# small_weather_station.net
KiCad netlist of a schematic drawn in EAGLE
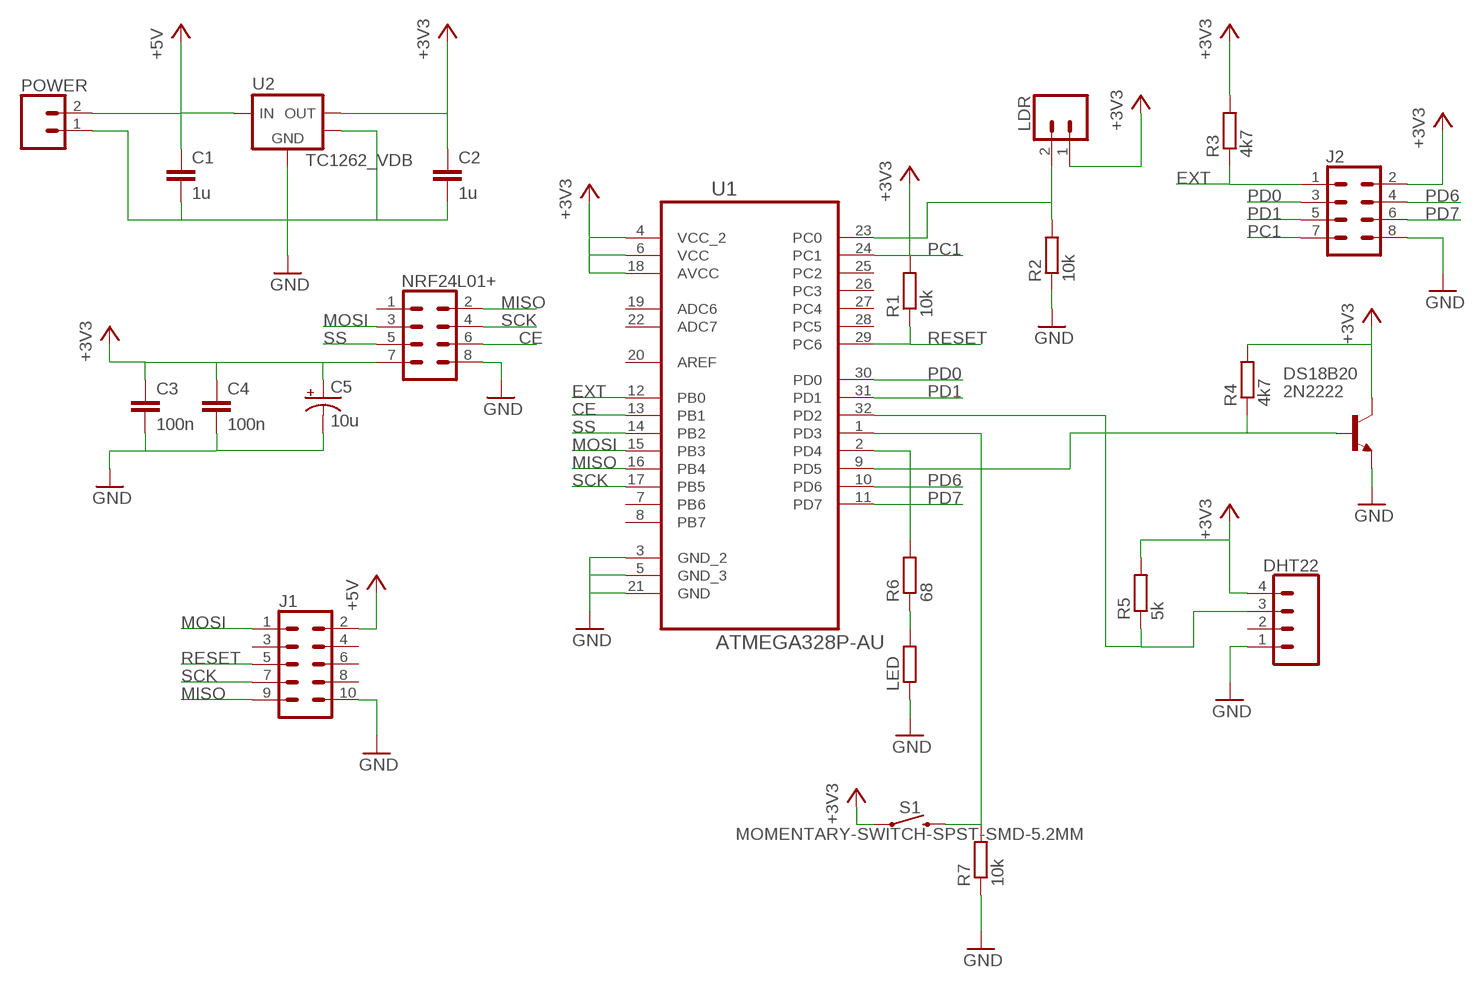
[diagram p0: schematic, sheet 1]

(export (version "E")
  (design (tool "Eeschema 10.0.6"))
  (components
    (comp (ref "C1")
      (value "1u")
      (footprint "eagle-import:C0402")
      (libsource (lib "eagle-import") (part "C-EUC0402"))
    )
    (comp (ref "C2")
      (value "1u")
      (footprint "eagle-import:C0402")
      (libsource (lib "eagle-import") (part "C-EUC0402"))
    )
    (comp (ref "C3")
      (value "100n")
      (footprint "eagle-import:C0402")
      (libsource (lib "eagle-import") (part "C-EUC0402"))
    )
    (comp (ref "C4")
      (value "100n")
      (footprint "eagle-import:C0402")
      (libsource (lib "eagle-import") (part "C-EUC0402"))
    )
    (comp (ref "C5")
      (value "10u")
      (footprint "eagle-import:PANASONIC_D")
      (libsource (lib "eagle-import") (part "CPOL-USD"))
    )
    (comp (ref "DHT22")
      (value "CONN_04")
      (footprint "eagle-import:1X04")
      (libsource (lib "eagle-import") (part "CONN_04"))
    )
    (comp (ref "DS18B20")
      (value "2N2222")
      (footprint "eagle-import:TO92-EBC-OVAL")
      (libsource (lib "eagle-import") (part "2N2222"))
    )
    (comp (ref "J1")
      (value "CONN_05X2SHD-NS")
      (footprint "eagle-import:2X5-SHROUDED-NS")
      (libsource (lib "eagle-import") (part "CONN_05X2SHD-NS"))
    )
    (comp (ref "J2")
      (value "CONN_04X2")
      (footprint "eagle-import:2X4")
      (libsource (lib "eagle-import") (part "CONN_04X2"))
    )
    (comp (ref "LDR")
      (value "CONN_02")
      (footprint "eagle-import:1X02")
      (libsource (lib "eagle-import") (part "CONN_02"))
    )
    (comp (ref "LED")
      (value "R-EU_R0402")
      (footprint "eagle-import:R0402")
      (libsource (lib "eagle-import") (part "R-EU_R0402"))
    )
    (comp (ref "NRF24L01+")
      (value "CONN_04X2")
      (footprint "eagle-import:2X4")
      (libsource (lib "eagle-import") (part "CONN_04X2"))
    )
    (comp (ref "POWER")
      (value "CONN_02")
      (footprint "eagle-import:1X02")
      (libsource (lib "eagle-import") (part "CONN_02"))
    )
    (comp (ref "R1")
      (value "10k")
      (footprint "eagle-import:R0402")
      (libsource (lib "eagle-import") (part "R-EU_R0402"))
    )
    (comp (ref "R2")
      (value "10k")
      (footprint "eagle-import:R0402")
      (libsource (lib "eagle-import") (part "R-EU_R0402"))
    )
    (comp (ref "R3")
      (value "4k7")
      (footprint "eagle-import:R0402")
      (libsource (lib "eagle-import") (part "R-EU_R0402"))
    )
    (comp (ref "R4")
      (value "4k7")
      (footprint "eagle-import:R0402")
      (libsource (lib "eagle-import") (part "R-EU_R0402"))
    )
    (comp (ref "R5")
      (value "5k")
      (footprint "eagle-import:R0402")
      (libsource (lib "eagle-import") (part "R-EU_R0402"))
    )
    (comp (ref "R6")
      (value "68")
      (footprint "eagle-import:R0402")
      (libsource (lib "eagle-import") (part "R-EU_R0402"))
    )
    (comp (ref "R7")
      (value "10k")
      (footprint "eagle-import:R0402")
      (libsource (lib "eagle-import") (part "R-EU_R0402"))
    )
    (comp (ref "S1")
      (value "MOMENTARY-SWITCH-SPST-SMD-5.2MM")
      (footprint "eagle-import:TACTILE_SWITCH_SMD_5.2MM")
      (libsource (lib "eagle-import") (part "MOMENTARY-SWITCH-SPST-SMD-5.2MM"))
    )
    (comp (ref "U1")
      (value "ATMEGA328P-AU")
      (footprint "eagle-import:QFP80P900X900X120-32N")
      (libsource (lib "eagle-import") (part "ATMEGA328P-AU"))
    )
    (comp (ref "U2")
      (value "TC1262_VDB")
      (footprint "eagle-import:SOT-223-3")
      (libsource (lib "eagle-import") (part "TC1262_VDB"))
    )
  )
  (nets
    (net (code "1") (name "+3V3") (class "Default")
      (node (ref "C2") (pin "1") (pinfunction "1_1") (pintype "passive"))
      (node (ref "C3") (pin "1") (pinfunction "1_1") (pintype "passive"))
      (node (ref "C4") (pin "1") (pinfunction "1_1") (pintype "passive"))
      (node (ref "C5") (pin "+") (pinfunction "+_+") (pintype "passive"))
      (node (ref "DHT22") (pin "4") (pinfunction "4_4") (pintype "passive"))
      (node (ref "DS18B20") (pin "C") (pinfunction "C_C") (pintype "passive"))
      (node (ref "J2") (pin "2") (pinfunction "2_2") (pintype "passive"))
      (node (ref "LDR") (pin "1") (pinfunction "1_1") (pintype "passive"))
      (node (ref "NRF24L01+") (pin "7") (pinfunction "7_7") (pintype "passive"))
      (node (ref "R1") (pin "2") (pinfunction "2_2") (pintype "passive"))
      (node (ref "R3") (pin "2") (pinfunction "2_2") (pintype "passive"))
      (node (ref "R4") (pin "2") (pinfunction "2_2") (pintype "passive"))
      (node (ref "R5") (pin "2") (pinfunction "2_2") (pintype "passive"))
      (node (ref "S1") (pin "1") (pinfunction "1_1") (pintype "passive"))
      (node (ref "U1") (pin "18") (pinfunction "AVCC_18") (pintype "power_in"))
      (node (ref "U1") (pin "4") (pinfunction "VCC_2_4") (pintype "power_in"))
      (node (ref "U1") (pin "6") (pinfunction "VCC_6") (pintype "power_in"))
      (node (ref "U2") (pin "3") (pinfunction "VOUT_3") (pintype "power_in"))
    )
    (net (code "2") (name "+5V") (class "Default")
      (node (ref "C1") (pin "1") (pinfunction "1_1") (pintype "passive"))
      (node (ref "J1") (pin "2") (pinfunction "2_2") (pintype "passive"))
      (node (ref "POWER") (pin "2") (pinfunction "2_2") (pintype "passive"))
      (node (ref "U2") (pin "1") (pinfunction "VIN_1") (pintype "power_in"))
    )
    (net (code "3") (name "/CE") (class "Default")
      (node (ref "NRF24L01+") (pin "6") (pinfunction "6_6") (pintype "passive"))
      (node (ref "U1") (pin "13") (pinfunction "PB1_13") (pintype "bidirectional"))
    )
    (net (code "4") (name "/EXT") (class "Default")
      (node (ref "J2") (pin "1") (pinfunction "1_1") (pintype "passive"))
      (node (ref "R3") (pin "1") (pinfunction "1_1") (pintype "passive"))
      (node (ref "U1") (pin "12") (pinfunction "PB0_12") (pintype "bidirectional"))
    )
    (net (code "5") (name "/MISO") (class "Default")
      (node (ref "J1") (pin "9") (pinfunction "9_9") (pintype "passive"))
      (node (ref "NRF24L01+") (pin "2") (pinfunction "2_2") (pintype "passive"))
      (node (ref "U1") (pin "16") (pinfunction "PB4_16") (pintype "bidirectional"))
    )
    (net (code "6") (name "/MOSI") (class "Default")
      (node (ref "J1") (pin "1") (pinfunction "1_1") (pintype "passive"))
      (node (ref "NRF24L01+") (pin "3") (pinfunction "3_3") (pintype "passive"))
      (node (ref "U1") (pin "15") (pinfunction "PB3_15") (pintype "bidirectional"))
    )
    (net (code "7") (name "/PC1") (class "Default")
      (node (ref "J2") (pin "7") (pinfunction "7_7") (pintype "passive"))
      (node (ref "U1") (pin "24") (pinfunction "PC1_24") (pintype "bidirectional"))
    )
    (net (code "8") (name "/PD0") (class "Default")
      (node (ref "J2") (pin "3") (pinfunction "3_3") (pintype "passive"))
      (node (ref "U1") (pin "30") (pinfunction "PD0_30") (pintype "bidirectional"))
    )
    (net (code "9") (name "/PD1") (class "Default")
      (node (ref "J2") (pin "5") (pinfunction "5_5") (pintype "passive"))
      (node (ref "U1") (pin "31") (pinfunction "PD1_31") (pintype "bidirectional"))
    )
    (net (code "10") (name "/PD6") (class "Default")
      (node (ref "J2") (pin "4") (pinfunction "4_4") (pintype "passive"))
      (node (ref "U1") (pin "10") (pinfunction "PD6_10") (pintype "bidirectional"))
    )
    (net (code "11") (name "/PD7") (class "Default")
      (node (ref "J2") (pin "6") (pinfunction "6_6") (pintype "passive"))
      (node (ref "U1") (pin "11") (pinfunction "PD7_11") (pintype "bidirectional"))
    )
    (net (code "12") (name "/RESET") (class "Default")
      (node (ref "J1") (pin "5") (pinfunction "5_5") (pintype "passive"))
      (node (ref "R1") (pin "1") (pinfunction "1_1") (pintype "passive"))
      (node (ref "U1") (pin "29") (pinfunction "PC6_29") (pintype "bidirectional"))
    )
    (net (code "13") (name "/SCK") (class "Default")
      (node (ref "J1") (pin "7") (pinfunction "7_7") (pintype "passive"))
      (node (ref "NRF24L01+") (pin "4") (pinfunction "4_4") (pintype "passive"))
      (node (ref "U1") (pin "17") (pinfunction "PB5_17") (pintype "bidirectional"))
    )
    (net (code "14") (name "/SS") (class "Default")
      (node (ref "NRF24L01+") (pin "5") (pinfunction "5_5") (pintype "passive"))
      (node (ref "U1") (pin "14") (pinfunction "PB2_14") (pintype "bidirectional"))
    )
    (net (code "15") (name "GND") (class "Default")
      (node (ref "C1") (pin "2") (pinfunction "2_2") (pintype "passive"))
      (node (ref "C2") (pin "2") (pinfunction "2_2") (pintype "passive"))
      (node (ref "C3") (pin "2") (pinfunction "2_2") (pintype "passive"))
      (node (ref "C4") (pin "2") (pinfunction "2_2") (pintype "passive"))
      (node (ref "C5") (pin "-") (pinfunction "-_-") (pintype "passive"))
      (node (ref "DHT22") (pin "1") (pinfunction "1_1") (pintype "passive"))
      (node (ref "DS18B20") (pin "E") (pinfunction "E_E") (pintype "passive"))
      (node (ref "J1") (pin "10") (pinfunction "10_10") (pintype "passive"))
      (node (ref "J2") (pin "8") (pinfunction "8_8") (pintype "passive"))
      (node (ref "LED") (pin "1") (pinfunction "1_1") (pintype "passive"))
      (node (ref "NRF24L01+") (pin "8") (pinfunction "8_8") (pintype "passive"))
      (node (ref "POWER") (pin "1") (pinfunction "1_1") (pintype "passive"))
      (node (ref "R2") (pin "1") (pinfunction "1_1") (pintype "passive"))
      (node (ref "R7") (pin "1") (pinfunction "1_1") (pintype "passive"))
      (node (ref "U1") (pin "21") (pinfunction "GND_21") (pintype "passive"))
      (node (ref "U1") (pin "3") (pinfunction "GND_2_3") (pintype "passive"))
      (node (ref "U1") (pin "5") (pinfunction "GND_3_5") (pintype "passive"))
      (node (ref "U2") (pin "2") (pinfunction "GND_2") (pintype "power_in"))
      (node (ref "U2") (pin "4") (pinfunction "TAB_4") (pintype "power_in"))
    )
    (net (code "16") (name "Net-(LED-Pad2)") (class "Default")
      (node (ref "LED") (pin "2") (pinfunction "2_2") (pintype "passive"))
      (node (ref "R6") (pin "1") (pinfunction "1_1") (pintype "passive"))
    )
    (net (code "17") (name "Net-(S1-2)") (class "Default")
      (node (ref "R7") (pin "2") (pinfunction "2_2") (pintype "passive"))
      (node (ref "S1") (pin "3") (pinfunction "2_3") (pintype "passive"))
      (node (ref "U1") (pin "1") (pinfunction "PD3_1") (pintype "bidirectional"))
    )
    (net (code "18") (name "Net-(U1-PC0)") (class "Default")
      (node (ref "LDR") (pin "2") (pinfunction "2_2") (pintype "passive"))
      (node (ref "R2") (pin "2") (pinfunction "2_2") (pintype "passive"))
      (node (ref "U1") (pin "23") (pinfunction "PC0_23") (pintype "bidirectional"))
    )
    (net (code "19") (name "Net-(U1-PD2)") (class "Default")
      (node (ref "DHT22") (pin "3") (pinfunction "3_3") (pintype "passive"))
      (node (ref "R5") (pin "1") (pinfunction "1_1") (pintype "passive"))
      (node (ref "U1") (pin "32") (pinfunction "PD2_32") (pintype "bidirectional"))
    )
    (net (code "20") (name "Net-(U1-PD4)") (class "Default")
      (node (ref "R6") (pin "2") (pinfunction "2_2") (pintype "passive"))
      (node (ref "U1") (pin "2") (pinfunction "PD4_2") (pintype "bidirectional"))
    )
    (net (code "21") (name "Net-(U1-PD5)") (class "Default")
      (node (ref "DS18B20") (pin "B") (pinfunction "B_B") (pintype "passive"))
      (node (ref "R4") (pin "1") (pinfunction "1_1") (pintype "passive"))
      (node (ref "U1") (pin "9") (pinfunction "PD5_9") (pintype "bidirectional"))
    )
    (net (code "22") (name "unconnected-(DHT22-Pad2)") (class "Default")
      (node (ref "DHT22") (pin "2") (pinfunction "2_2") (pintype "passive"))
    )
    (net (code "23") (name "unconnected-(J1-Pad3)") (class "Default")
      (node (ref "J1") (pin "3") (pinfunction "3_3") (pintype "passive"))
    )
    (net (code "24") (name "unconnected-(J1-Pad4)") (class "Default")
      (node (ref "J1") (pin "4") (pinfunction "4_4") (pintype "passive"))
    )
    (net (code "25") (name "unconnected-(J1-Pad6)") (class "Default")
      (node (ref "J1") (pin "6") (pinfunction "6_6") (pintype "passive"))
    )
    (net (code "26") (name "unconnected-(J1-Pad8)") (class "Default")
      (node (ref "J1") (pin "8") (pinfunction "8_8") (pintype "passive"))
    )
    (net (code "27") (name "unconnected-(NRF24L01+-Pad1)") (class "Default")
      (node (ref "NRF24L01+") (pin "1") (pinfunction "1_1") (pintype "passive"))
    )
    (net (code "28") (name "unconnected-(U1-ADC6-Pad19)") (class "Default")
      (node (ref "U1") (pin "19") (pinfunction "ADC6_19") (pintype "input"))
    )
    (net (code "29") (name "unconnected-(U1-ADC7-Pad22)") (class "Default")
      (node (ref "U1") (pin "22") (pinfunction "ADC7_22") (pintype "input"))
    )
    (net (code "30") (name "unconnected-(U1-AREF-Pad20)") (class "Default")
      (node (ref "U1") (pin "20") (pinfunction "AREF_20") (pintype "input"))
    )
    (net (code "31") (name "unconnected-(U1-PB6-Pad7)") (class "Default")
      (node (ref "U1") (pin "7") (pinfunction "PB6_7") (pintype "bidirectional"))
    )
    (net (code "32") (name "unconnected-(U1-PB7-Pad8)") (class "Default")
      (node (ref "U1") (pin "8") (pinfunction "PB7_8") (pintype "bidirectional"))
    )
    (net (code "33") (name "unconnected-(U1-PC2-Pad25)") (class "Default")
      (node (ref "U1") (pin "25") (pinfunction "PC2_25") (pintype "bidirectional"))
    )
    (net (code "34") (name "unconnected-(U1-PC3-Pad26)") (class "Default")
      (node (ref "U1") (pin "26") (pinfunction "PC3_26") (pintype "bidirectional"))
    )
    (net (code "35") (name "unconnected-(U1-PC4-Pad27)") (class "Default")
      (node (ref "U1") (pin "27") (pinfunction "PC4_27") (pintype "bidirectional"))
    )
    (net (code "36") (name "unconnected-(U1-PC5-Pad28)") (class "Default")
      (node (ref "U1") (pin "28") (pinfunction "PC5_28") (pintype "bidirectional"))
    )
  )
)
